# 5V_1A_LDO_SUPPLY.net
KiCad netlist of a schematic drawn in Altium Designer
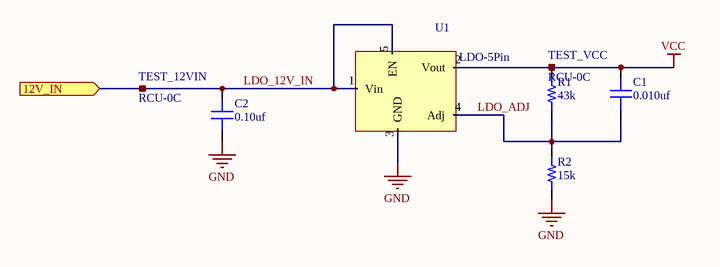
[diagram p0: 5V_1A_LDO_SUPPLY.SchDoc]

(export (version "E")
  (design (tool "Eeschema 10.0.6"))
  (components
    (comp (ref "C1")
      (value "0.010uf")
      (footprint "CAP 0603/1608")
      (fields
        (field (name "Comment") "Capacitor MLCC 0.010uf 16V CAP 0603/1608")
        (field (name "CREATED_BY") "Nick Mah")
      )
      (libsource (lib "Altium-Lib") (part "Capacitor"))
    )
    (comp (ref "C2")
      (value "0.10uf")
      (footprint "CAP 0603/1608")
      (fields
        (field (name "Comment") "Capacitor MLCC 0.10uf 16V CAP 0603/1608")
        (field (name "CREATED_BY") "Nick Mah")
      )
      (libsource (lib "Altium-Lib") (part "Capacitor"))
    )
    (comp (ref "R1")
      (value "43k")
      (footprint "RES 0603/1608")
      (fields
        (field (name "TOLERANCE") "1%")
        (field (name "POWER") "1/10W")
        (field (name "Comment") "Resistor 43k 0603 1/10W 1%")
        (field (name "CREATED_BY") "Nick Mah")
      )
      (libsource (lib "Altium-Lib") (part "Resistor"))
    )
    (comp (ref "R2")
      (value "15k")
      (footprint "RES 0603/1608")
      (fields
        (field (name "TOLERANCE") "1%")
        (field (name "POWER") "1/10W")
        (field (name "Comment") "Resistor 15k 0603 1/10W 1%")
        (field (name "CREATED_BY") "Nick Mah")
      )
      (libsource (lib "Altium-Lib") (part "Resistor"))
    )
    (comp (ref "TEST_12VIN")
      (value "RCU-0C")
      (footprint "RCU-0C")
      (libsource (lib "Altium-Lib") (part "RCU-0C"))
    )
    (comp (ref "TEST_VCC")
      (value "RCU-0C")
      (footprint "RCU-0C")
      (libsource (lib "Altium-Lib") (part "RCU-0C"))
    )
    (comp (ref "U1")
      (value "LDO-5Pin")
      (footprint "SOT223-5")
      (fields (field (name "MFRPARTNO") "REG104GA-A"))
      (libsource (lib "Altium-Lib") (part "LDO-5Pin"))
    )
  )
  (nets
    (net (code "1") (name "/LDO_12V_IN") (class "Default")
      (node (ref "C2") (pin "2") (pinfunction "2_2") (pintype "passive"))
      (node (ref "TEST_12VIN") (pin "1") (pintype "passive"))
      (node (ref "U1") (pin "1") (pinfunction "Vin_1") (pintype "input"))
      (node (ref "U1") (pin "5") (pinfunction "EN_5") (pintype "input"))
    )
    (net (code "2") (name "/LDO_ADJ") (class "Default")
      (node (ref "C1") (pin "1") (pinfunction "1_1") (pintype "passive"))
      (node (ref "R1") (pin "1") (pinfunction "1_1") (pintype "passive"))
      (node (ref "R2") (pin "2") (pinfunction "2_2") (pintype "passive"))
      (node (ref "U1") (pin "4") (pinfunction "Adj_4") (pintype "input"))
    )
    (net (code "3") (name "GND") (class "Default")
      (node (ref "C2") (pin "1") (pinfunction "1_1") (pintype "passive"))
      (node (ref "R2") (pin "1") (pinfunction "1_1") (pintype "passive"))
      (node (ref "U1") (pin "3") (pinfunction "GND_3") (pintype "input"))
    )
    (net (code "4") (name "VCC") (class "Default")
      (node (ref "C1") (pin "2") (pinfunction "2_2") (pintype "passive"))
      (node (ref "R1") (pin "2") (pinfunction "2_2") (pintype "passive"))
      (node (ref "TEST_VCC") (pin "1") (pintype "passive"))
      (node (ref "U1") (pin "2") (pinfunction "Vout_2") (pintype "input"))
    )
  )
)
